# easyeda_SCH.net
KiCad netlist of a schematic drawn in EasyEDA
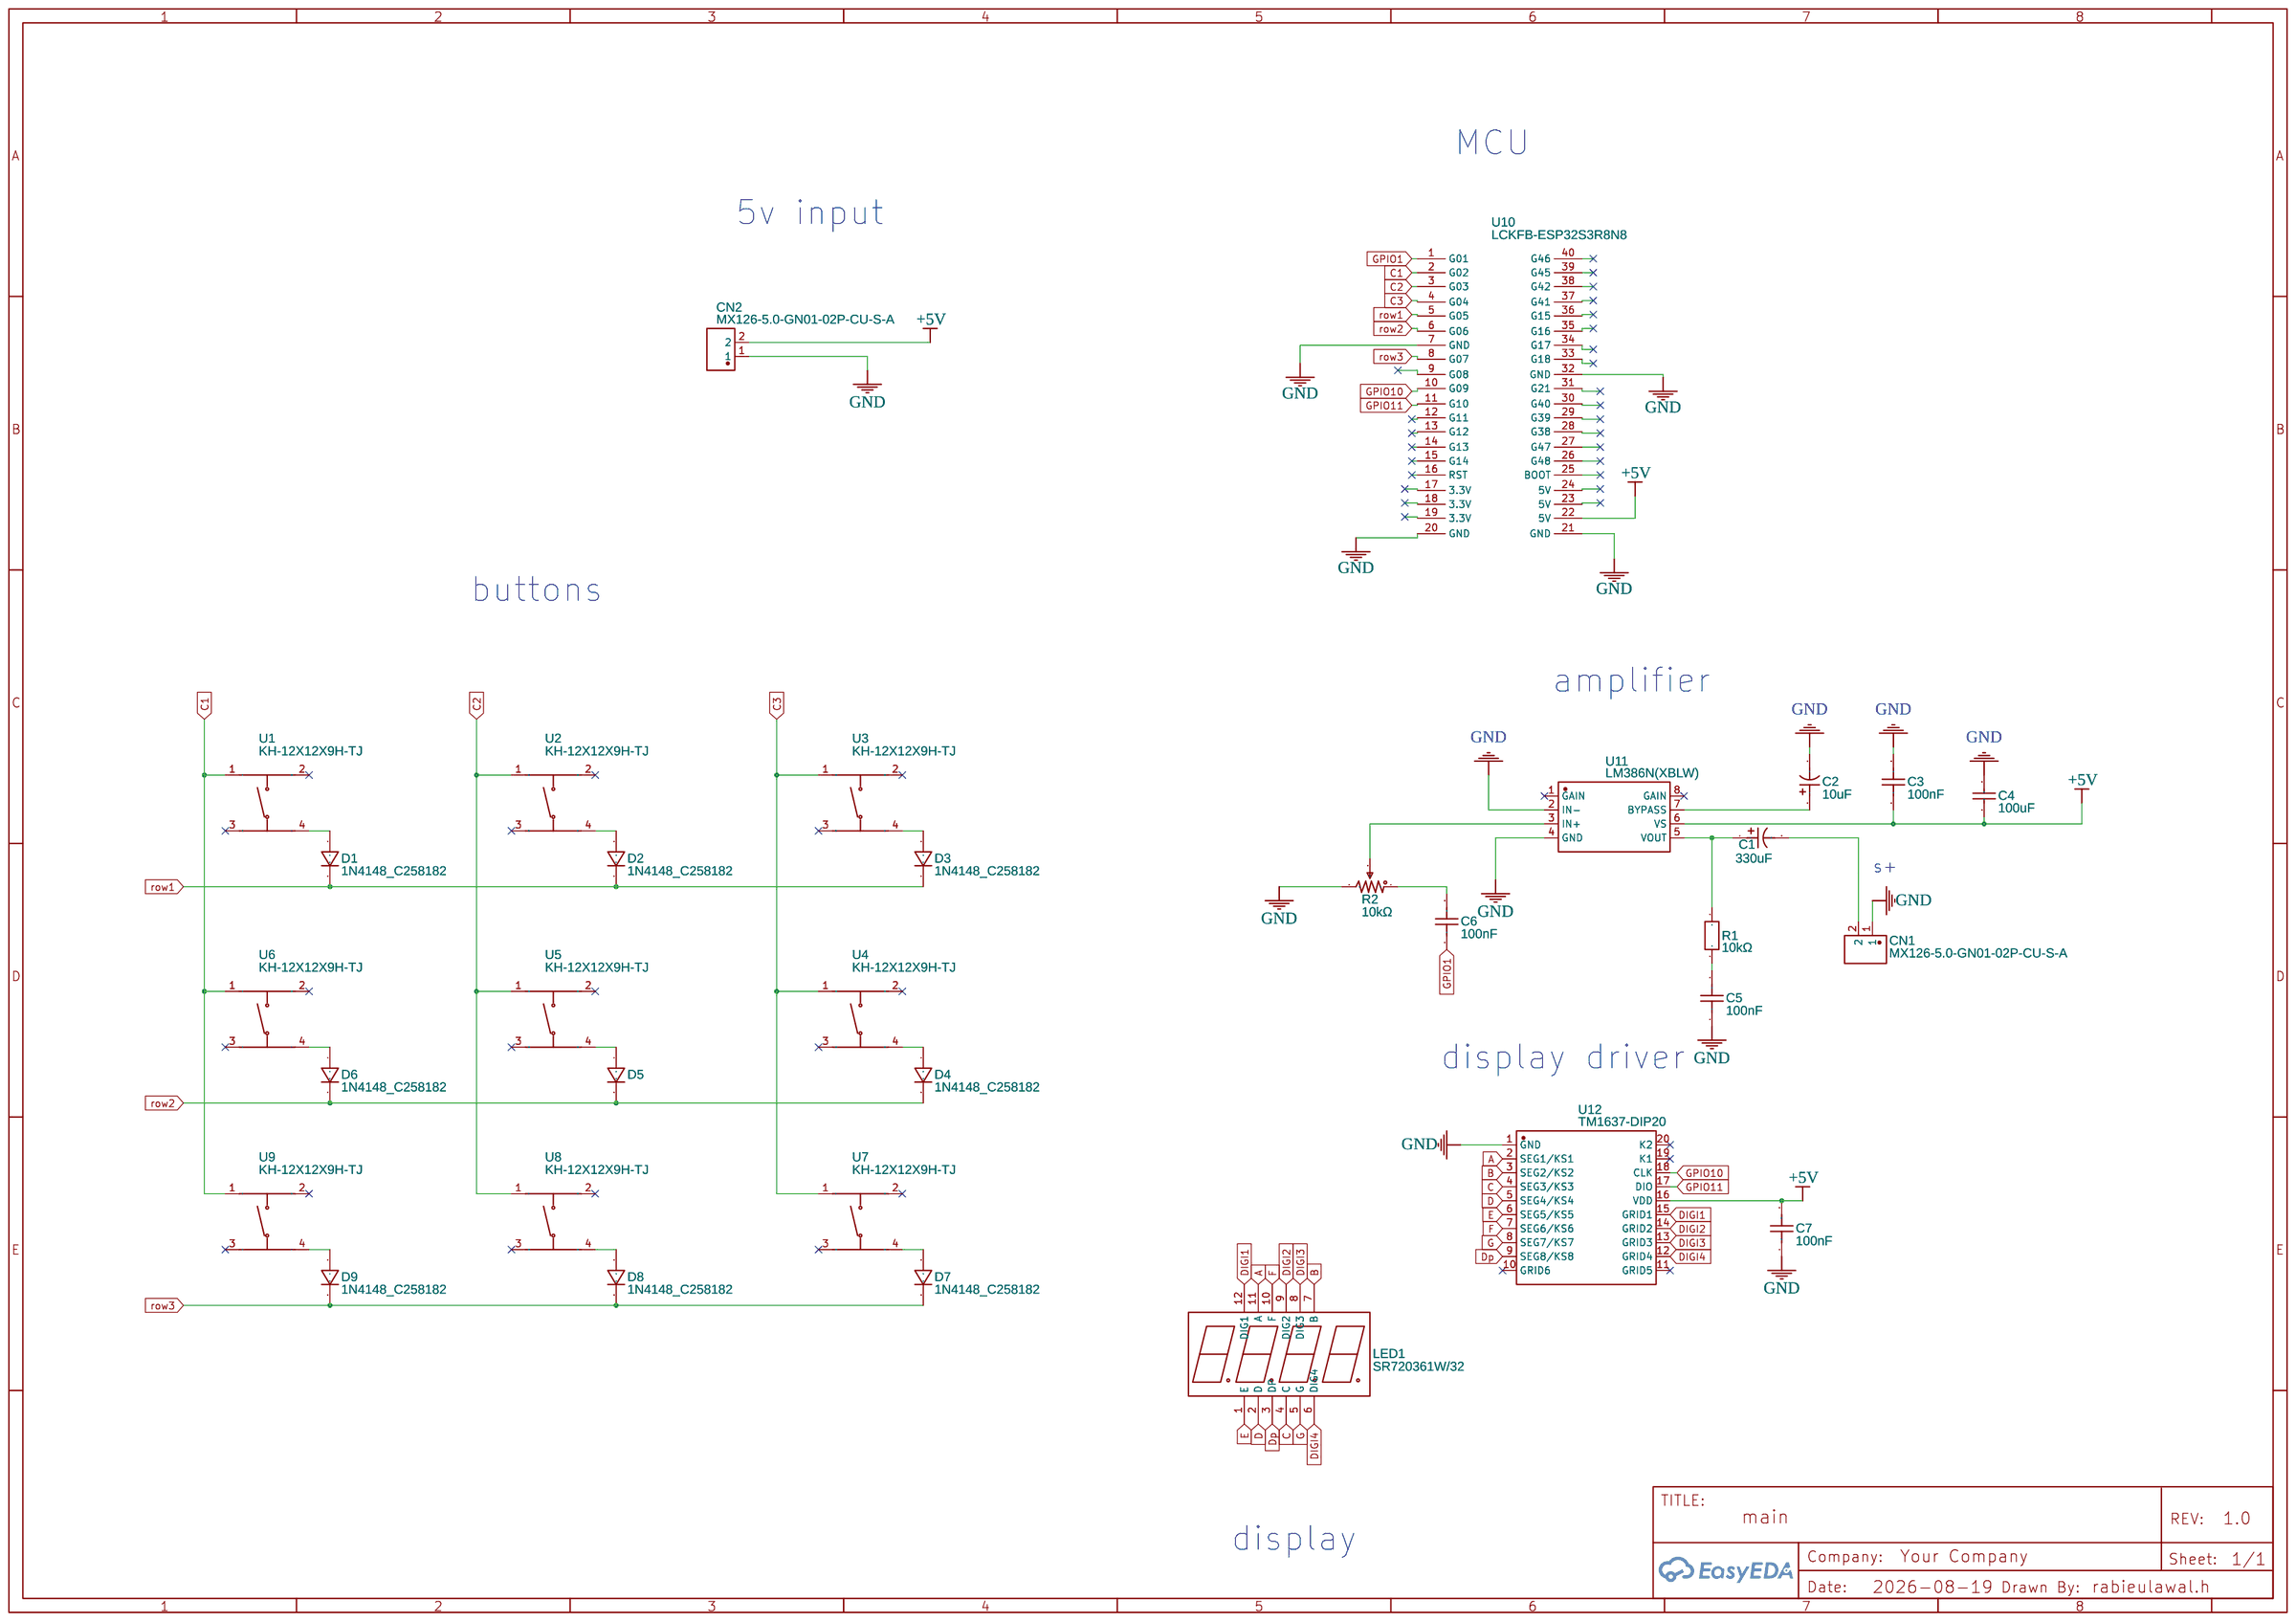
[diagram p0: schematic sheet]

(export (version "E")
  (design (tool "Eeschema 10.0.6"))
  (components
    (comp (ref "C1")
      (value "330uF")
      (fields
        (field (name "Manufacturer Part") "330uF10V6.3x11GF")
        (field (name "Manufacturer") "Econd(米朗电子)")
      )
      (libsource (lib "") (part "330UF10V6.3X11GF"))
    )
    (comp (ref "C2")
      (value "10uF")
      (fields (field (name "Manufacturer Part") "CG100ME511BP") (field (name "Manufacturer") "TWBOR(伯鸿)"))
      (libsource (lib "") (part "CG100ME511BP"))
    )
    (comp (ref "C3")
      (value "100nF")
      (fields (field (name "Manufacturer Part") "FM32X104K101EMG") (field (name "Manufacturer") "PSA(信昌电陶)"))
      (libsource (lib "") (part "FM32X104K101EMG"))
    )
    (comp (ref "C4")
      (value "100uF")
      (fields
        (field (name "Manufacturer Part") "CL32A107MQVNNNE")
        (field (name "Manufacturer") "SAMSUNG(三星)")
      )
      (libsource (lib "") (part "CL32A107MQVNNNE"))
    )
    (comp (ref "C5")
      (value "100nF")
      (fields (field (name "Manufacturer Part") "FM32X104K101EMG") (field (name "Manufacturer") "PSA(信昌电陶)"))
      (libsource (lib "") (part "FM32X104K101EMG"))
    )
    (comp (ref "C6")
      (value "100nF")
      (fields (field (name "Manufacturer Part") "FM32X104K101EMG") (field (name "Manufacturer") "PSA(信昌电陶)"))
      (libsource (lib "") (part "FM32X104K101EMG"))
    )
    (comp (ref "C7")
      (value "100nF")
      (fields (field (name "Manufacturer Part") "FM32X104K101EMG") (field (name "Manufacturer") "PSA(信昌电陶)"))
      (libsource (lib "") (part "FM32X104K101EMG"))
    )
    (comp (ref "CN1")
      (value "MX126-5.0-GN01-02P-CU-S-A")
      (fields
        (field (name "Manufacturer Part") "MX126-5.0-02P-GN01-Cu-S-A")
        (field (name "Manufacturer") "MAX(迈旭)")
      )
      (libsource (lib "") (part "MX126-5.0-GN01-02P-CU-S-A"))
    )
    (comp (ref "CN2")
      (value "MX126-5.0-GN01-02P-CU-S-A")
      (fields
        (field (name "Manufacturer Part") "MX126-5.0-02P-GN01-Cu-S-A")
        (field (name "Manufacturer") "MAX(迈旭)")
      )
      (libsource (lib "") (part "MX126-5.0-GN01-02P-CU-S-A_1"))
    )
    (comp (ref "D1")
      (value "1N4148_C258182")
      (fields (field (name "Manufacturer Part") "1N4148") (field (name "Manufacturer") "onsemi(安森美)"))
      (libsource (lib "") (part "1N4148_C258182"))
    )
    (comp (ref "D2")
      (value "1N4148_C258182")
      (fields (field (name "Manufacturer Part") "1N4148") (field (name "Manufacturer") "onsemi(安森美)"))
      (libsource (lib "") (part "1N4148_C258182"))
    )
    (comp (ref "D3")
      (value "1N4148_C258182")
      (fields (field (name "Manufacturer Part") "1N4148") (field (name "Manufacturer") "onsemi(安森美)"))
      (libsource (lib "") (part "1N4148_C258182"))
    )
    (comp (ref "D4")
      (value "1N4148_C258182")
      (fields (field (name "Manufacturer Part") "1N4148") (field (name "Manufacturer") "onsemi(安森美)"))
      (libsource (lib "") (part "1N4148_C258182"))
    )
    (comp (ref "D5")
      (value "1N4148_C258182")
      (fields (field (name "Manufacturer Part") "1N4148") (field (name "Manufacturer") "onsemi(安森美)"))
      (libsource (lib "") (part "1N4148_C258182"))
    )
    (comp (ref "D6")
      (value "1N4148_C258182")
      (fields (field (name "Manufacturer Part") "1N4148") (field (name "Manufacturer") "onsemi(安森美)"))
      (libsource (lib "") (part "1N4148_C258182"))
    )
    (comp (ref "D7")
      (value "1N4148_C258182")
      (fields (field (name "Manufacturer Part") "1N4148") (field (name "Manufacturer") "onsemi(安森美)"))
      (libsource (lib "") (part "1N4148_C258182"))
    )
    (comp (ref "D8")
      (value "1N4148_C258182")
      (fields (field (name "Manufacturer Part") "1N4148") (field (name "Manufacturer") "onsemi(安森美)"))
      (libsource (lib "") (part "1N4148_C258182"))
    )
    (comp (ref "D9")
      (value "1N4148_C258182")
      (fields (field (name "Manufacturer Part") "1N4148") (field (name "Manufacturer") "onsemi(安森美)"))
      (libsource (lib "") (part "1N4148_C258182"))
    )
    (comp (ref "LED1")
      (value "SR720361W/32")
      (fields (field (name "Manufacturer") "ARKLED(方舟)"))
      (libsource (lib "") (part "SR720361W/32"))
    )
    (comp (ref "R1")
      (value "10kΩ")
      (fields (field (name "Manufacturer Part") "CR1/8W-10K±5%-ST52") (field (name "Manufacturer") "VO(翔胜)"))
      (libsource (lib "") (part "CR1/8W-10K±5%-ST52"))
    )
    (comp (ref "R2")
      (value "10kΩ")
      (fields
        (field (name "Manufacturer Part") "RK09Y11L0001")
        (field (name "Manufacturer") "ALPSALPINE(阿尔卑斯阿尔派)")
      )
      (libsource (lib "") (part "RK09Y11L0001"))
    )
    (comp (ref "U1")
      (value "KH-12X12X9H-TJ")
      (fields (field (name "Manufacturer") "kinghelm(金航标)"))
      (libsource (lib "") (part "KH-12X12X9H-TJ"))
    )
    (comp (ref "U2")
      (value "KH-12X12X9H-TJ")
      (fields (field (name "Manufacturer") "kinghelm(金航标)"))
      (libsource (lib "") (part "KH-12X12X9H-TJ"))
    )
    (comp (ref "U3")
      (value "KH-12X12X9H-TJ")
      (fields (field (name "Manufacturer") "kinghelm(金航标)"))
      (libsource (lib "") (part "KH-12X12X9H-TJ"))
    )
    (comp (ref "U4")
      (value "KH-12X12X9H-TJ")
      (fields (field (name "Manufacturer") "kinghelm(金航标)"))
      (libsource (lib "") (part "KH-12X12X9H-TJ"))
    )
    (comp (ref "U5")
      (value "KH-12X12X9H-TJ")
      (fields (field (name "Manufacturer") "kinghelm(金航标)"))
      (libsource (lib "") (part "KH-12X12X9H-TJ"))
    )
    (comp (ref "U6")
      (value "KH-12X12X9H-TJ")
      (fields (field (name "Manufacturer") "kinghelm(金航标)"))
      (libsource (lib "") (part "KH-12X12X9H-TJ"))
    )
    (comp (ref "U7")
      (value "KH-12X12X9H-TJ")
      (fields (field (name "Manufacturer") "kinghelm(金航标)"))
      (libsource (lib "") (part "KH-12X12X9H-TJ"))
    )
    (comp (ref "U8")
      (value "KH-12X12X9H-TJ")
      (fields (field (name "Manufacturer") "kinghelm(金航标)"))
      (libsource (lib "") (part "KH-12X12X9H-TJ"))
    )
    (comp (ref "U9")
      (value "KH-12X12X9H-TJ")
      (fields (field (name "Manufacturer") "kinghelm(金航标)"))
      (libsource (lib "") (part "KH-12X12X9H-TJ"))
    )
    (comp (ref "U10")
      (value "LCKFB-ESP32S3R8N8")
      (fields (field (name "Manufacturer") "立创开发板"))
      (libsource (lib "") (part "LCKFB-ESP32S3R8N8"))
    )
    (comp (ref "U11")
      (value "LM386N(XBLW)")
      (fields (field (name "Manufacturer") "XBLW(芯伯乐)"))
      (libsource (lib "") (part "LM386N(XBLW)"))
    )
    (comp (ref "U12")
      (value "TM1637-DIP20")
      (fields (field (name "Manufacturer") "TM(天微)"))
      (libsource (lib "") (part "TM1637-DIP20"))
    )
  )
  (nets
    (net (code "1") (name "+5V") (class "Default")
      (node (ref "C3") (pin "1") (pinfunction "1_1") (pintype "unspecified"))
      (node (ref "C4") (pin "1") (pinfunction "1_1") (pintype "input"))
      (node (ref "C7") (pin "2") (pinfunction "2_2") (pintype "unspecified"))
      (node (ref "CN2") (pin "2") (pinfunction "2_2") (pintype "unspecified"))
      (node (ref "U10") (pin "22") (pinfunction "5V_22") (pintype "unspecified"))
      (node (ref "U11") (pin "6") (pinfunction "VS_6") (pintype "unspecified"))
      (node (ref "U12") (pin "16") (pinfunction "VDD_16") (pintype "unspecified"))
    )
    (net (code "2") (name "A") (class "Default")
      (node (ref "LED1") (pin "11") (pinfunction "A_11") (pintype "unspecified"))
      (node (ref "U12") (pin "2") (pinfunction "SEG1/KS1_2") (pintype "unspecified"))
    )
    (net (code "3") (name "B") (class "Default")
      (node (ref "LED1") (pin "7") (pinfunction "B_7") (pintype "unspecified"))
      (node (ref "U12") (pin "3") (pinfunction "SEG2/KS2_3") (pintype "unspecified"))
    )
    (net (code "4") (name "C") (class "Default")
      (node (ref "LED1") (pin "4") (pinfunction "C_4") (pintype "unspecified"))
      (node (ref "U12") (pin "4") (pinfunction "SEG3/KS3_4") (pintype "unspecified"))
    )
    (net (code "5") (name "C1") (class "Default")
      (node (ref "U1") (pin "1") (pinfunction "1_1") (pintype "unspecified"))
      (node (ref "U10") (pin "2") (pinfunction "G02_2") (pintype "unspecified"))
      (node (ref "U6") (pin "1") (pinfunction "1_1") (pintype "unspecified"))
      (node (ref "U9") (pin "1") (pinfunction "1_1") (pintype "unspecified"))
    )
    (net (code "6") (name "C2") (class "Default")
      (node (ref "U10") (pin "3") (pinfunction "G03_3") (pintype "unspecified"))
      (node (ref "U2") (pin "1") (pinfunction "1_1") (pintype "unspecified"))
      (node (ref "U5") (pin "1") (pinfunction "1_1") (pintype "unspecified"))
      (node (ref "U8") (pin "1") (pinfunction "1_1") (pintype "unspecified"))
    )
    (net (code "7") (name "C3") (class "Default")
      (node (ref "U10") (pin "4") (pinfunction "G04_4") (pintype "unspecified"))
      (node (ref "U3") (pin "1") (pinfunction "1_1") (pintype "unspecified"))
      (node (ref "U4") (pin "1") (pinfunction "1_1") (pintype "unspecified"))
      (node (ref "U7") (pin "1") (pinfunction "1_1") (pintype "unspecified"))
    )
    (net (code "8") (name "D") (class "Default")
      (node (ref "LED1") (pin "2") (pinfunction "D_2") (pintype "unspecified"))
      (node (ref "U12") (pin "5") (pinfunction "SEG4/KS4_5") (pintype "unspecified"))
    )
    (net (code "9") (name "DIGI1") (class "Default")
      (node (ref "LED1") (pin "12") (pinfunction "DIG1_12") (pintype "unspecified"))
      (node (ref "U12") (pin "15") (pinfunction "GRID1_15") (pintype "unspecified"))
    )
    (net (code "10") (name "DIGI2") (class "Default")
      (node (ref "LED1") (pin "9") (pinfunction "DIG2_9") (pintype "unspecified"))
      (node (ref "U12") (pin "14") (pinfunction "GRID2_14") (pintype "unspecified"))
    )
    (net (code "11") (name "DIGI3") (class "Default")
      (node (ref "LED1") (pin "8") (pinfunction "DIG3_8") (pintype "unspecified"))
      (node (ref "U12") (pin "13") (pinfunction "GRID3_13") (pintype "unspecified"))
    )
    (net (code "12") (name "DIGI4") (class "Default")
      (node (ref "LED1") (pin "6") (pinfunction "DIG4_6") (pintype "unspecified"))
      (node (ref "U12") (pin "12") (pinfunction "GRID4_12") (pintype "unspecified"))
    )
    (net (code "13") (name "Dp") (class "Default")
      (node (ref "LED1") (pin "3") (pinfunction "DP_3") (pintype "unspecified"))
      (node (ref "U12") (pin "9") (pinfunction "SEG8/KS8_9") (pintype "unspecified"))
    )
    (net (code "14") (name "E") (class "Default")
      (node (ref "LED1") (pin "1") (pinfunction "E_1") (pintype "unspecified"))
      (node (ref "U12") (pin "6") (pinfunction "SEG5/KS5_6") (pintype "unspecified"))
    )
    (net (code "15") (name "F") (class "Default")
      (node (ref "LED1") (pin "10") (pinfunction "F_10") (pintype "unspecified"))
      (node (ref "U12") (pin "7") (pinfunction "SEG6/KS6_7") (pintype "unspecified"))
    )
    (net (code "16") (name "G") (class "Default")
      (node (ref "LED1") (pin "5") (pinfunction "G_5") (pintype "unspecified"))
      (node (ref "U12") (pin "8") (pinfunction "SEG7/KS7_8") (pintype "unspecified"))
    )
    (net (code "17") (name "GND") (class "Default")
      (node (ref "C2") (pin "2") (pinfunction "2_2") (pintype "input"))
      (node (ref "C3") (pin "2") (pinfunction "2_2") (pintype "unspecified"))
      (node (ref "C4") (pin "2") (pinfunction "2_2") (pintype "input"))
      (node (ref "C5") (pin "1") (pinfunction "1_1") (pintype "unspecified"))
      (node (ref "C7") (pin "1") (pinfunction "1_1") (pintype "unspecified"))
      (node (ref "CN1") (pin "1") (pinfunction "1_1") (pintype "unspecified"))
      (node (ref "CN2") (pin "1") (pinfunction "1_1") (pintype "unspecified"))
      (node (ref "R2") (pin "3") (pinfunction "3_3") (pintype "unspecified"))
      (node (ref "U10") (pin "20") (pinfunction "GND_20") (pintype "unspecified"))
      (node (ref "U10") (pin "21") (pinfunction "GND_21") (pintype "unspecified"))
      (node (ref "U10") (pin "32") (pinfunction "GND_32") (pintype "unspecified"))
      (node (ref "U10") (pin "7") (pinfunction "GND_7") (pintype "unspecified"))
      (node (ref "U11") (pin "2") (pinfunction "IN-_2") (pintype "unspecified"))
      (node (ref "U11") (pin "4") (pinfunction "GND_4") (pintype "unspecified"))
      (node (ref "U12") (pin "1") (pinfunction "GND_1") (pintype "unspecified"))
    )
    (net (code "18") (name "GPIO1") (class "Default")
      (node (ref "C6") (pin "1") (pinfunction "1_1") (pintype "unspecified"))
      (node (ref "U10") (pin "1") (pinfunction "G01_1") (pintype "unspecified"))
    )
    (net (code "19") (name "GPIO10") (class "Default")
      (node (ref "U10") (pin "10") (pinfunction "G09_10") (pintype "unspecified"))
      (node (ref "U12") (pin "18") (pinfunction "CLK_18") (pintype "unspecified"))
    )
    (net (code "20") (name "GPIO11") (class "Default")
      (node (ref "U10") (pin "11") (pinfunction "G10_11") (pintype "unspecified"))
      (node (ref "U12") (pin "17") (pinfunction "DIO_17") (pintype "unspecified"))
    )
    (net (code "21") (name "Net-(C1-Pad2)") (class "Default")
      (node (ref "C1") (pin "2") (pinfunction "2_2") (pintype "input"))
      (node (ref "CN1") (pin "2") (pinfunction "2_2") (pintype "unspecified"))
    )
    (net (code "22") (name "Net-(C5-Pad2)") (class "Default")
      (node (ref "C5") (pin "2") (pinfunction "2_2") (pintype "unspecified"))
      (node (ref "R1") (pin "1") (pinfunction "1_1") (pintype "unspecified"))
    )
    (net (code "23") (name "Net-(C6-Pad2)") (class "Default")
      (node (ref "C6") (pin "2") (pinfunction "2_2") (pintype "unspecified"))
      (node (ref "R2") (pin "1") (pinfunction "1_1") (pintype "unspecified"))
    )
    (net (code "24") (name "Net-(D1-A)") (class "Default")
      (node (ref "D1") (pin "1") (pinfunction "A_1") (pintype "unspecified"))
      (node (ref "U1") (pin "4") (pinfunction "4_4") (pintype "unspecified"))
    )
    (net (code "25") (name "Net-(D2-A)") (class "Default")
      (node (ref "D2") (pin "1") (pinfunction "A_1") (pintype "unspecified"))
      (node (ref "U2") (pin "4") (pinfunction "4_4") (pintype "unspecified"))
    )
    (net (code "26") (name "Net-(D3-A)") (class "Default")
      (node (ref "D3") (pin "1") (pinfunction "A_1") (pintype "unspecified"))
      (node (ref "U3") (pin "4") (pinfunction "4_4") (pintype "unspecified"))
    )
    (net (code "27") (name "Net-(D4-A)") (class "Default")
      (node (ref "D4") (pin "1") (pinfunction "A_1") (pintype "unspecified"))
      (node (ref "U4") (pin "4") (pinfunction "4_4") (pintype "unspecified"))
    )
    (net (code "28") (name "Net-(D5-A)") (class "Default")
      (node (ref "D5") (pin "1") (pinfunction "A_1") (pintype "unspecified"))
      (node (ref "U5") (pin "4") (pinfunction "4_4") (pintype "unspecified"))
    )
    (net (code "29") (name "Net-(D6-A)") (class "Default")
      (node (ref "D6") (pin "1") (pinfunction "A_1") (pintype "unspecified"))
      (node (ref "U6") (pin "4") (pinfunction "4_4") (pintype "unspecified"))
    )
    (net (code "30") (name "Net-(D7-A)") (class "Default")
      (node (ref "D7") (pin "1") (pinfunction "A_1") (pintype "unspecified"))
      (node (ref "U7") (pin "4") (pinfunction "4_4") (pintype "unspecified"))
    )
    (net (code "31") (name "Net-(D8-A)") (class "Default")
      (node (ref "D8") (pin "1") (pinfunction "A_1") (pintype "unspecified"))
      (node (ref "U8") (pin "4") (pinfunction "4_4") (pintype "unspecified"))
    )
    (net (code "32") (name "Net-(D9-A)") (class "Default")
      (node (ref "D9") (pin "1") (pinfunction "A_1") (pintype "unspecified"))
      (node (ref "U9") (pin "4") (pinfunction "4_4") (pintype "unspecified"))
    )
    (net (code "33") (name "Net-(U11-BYPASS)") (class "Default")
      (node (ref "C2") (pin "1") (pinfunction "1_1") (pintype "input"))
      (node (ref "U11") (pin "7") (pinfunction "BYPASS_7") (pintype "unspecified"))
    )
    (net (code "34") (name "Net-(U11-IN+)") (class "Default")
      (node (ref "R2") (pin "2") (pinfunction "2_2") (pintype "unspecified"))
      (node (ref "U11") (pin "3") (pinfunction "IN+_3") (pintype "unspecified"))
    )
    (net (code "35") (name "Net-(U11-VOUT)") (class "Default")
      (node (ref "C1") (pin "1") (pinfunction "1_1") (pintype "input"))
      (node (ref "R1") (pin "2") (pinfunction "2_2") (pintype "unspecified"))
      (node (ref "U11") (pin "5") (pinfunction "VOUT_5") (pintype "unspecified"))
    )
    (net (code "36") (name "row1") (class "Default")
      (node (ref "D1") (pin "2") (pinfunction "K_2") (pintype "unspecified"))
      (node (ref "D2") (pin "2") (pinfunction "K_2") (pintype "unspecified"))
      (node (ref "D3") (pin "2") (pinfunction "K_2") (pintype "unspecified"))
      (node (ref "U10") (pin "5") (pinfunction "G05_5") (pintype "unspecified"))
    )
    (net (code "37") (name "row2") (class "Default")
      (node (ref "D4") (pin "2") (pinfunction "K_2") (pintype "unspecified"))
      (node (ref "D5") (pin "2") (pinfunction "K_2") (pintype "unspecified"))
      (node (ref "D6") (pin "2") (pinfunction "K_2") (pintype "unspecified"))
      (node (ref "U10") (pin "6") (pinfunction "G06_6") (pintype "unspecified"))
    )
    (net (code "38") (name "row3") (class "Default")
      (node (ref "D7") (pin "2") (pinfunction "K_2") (pintype "unspecified"))
      (node (ref "D8") (pin "2") (pinfunction "K_2") (pintype "unspecified"))
      (node (ref "D9") (pin "2") (pinfunction "K_2") (pintype "unspecified"))
      (node (ref "U10") (pin "8") (pinfunction "G07_8") (pintype "unspecified"))
    )
    (net (code "39") (name "unconnected-(U1-Pad2)") (class "Default")
      (node (ref "U1") (pin "2") (pinfunction "2_2") (pintype "unspecified+no_connect"))
    )
    (net (code "40") (name "unconnected-(U1-Pad3)") (class "Default")
      (node (ref "U1") (pin "3") (pinfunction "3_3") (pintype "unspecified+no_connect"))
    )
    (net (code "41") (name "unconnected-(U2-Pad2)") (class "Default")
      (node (ref "U2") (pin "2") (pinfunction "2_2") (pintype "unspecified+no_connect"))
    )
    (net (code "42") (name "unconnected-(U2-Pad3)") (class "Default")
      (node (ref "U2") (pin "3") (pinfunction "3_3") (pintype "unspecified+no_connect"))
    )
    (net (code "43") (name "unconnected-(U3-Pad2)") (class "Default")
      (node (ref "U3") (pin "2") (pinfunction "2_2") (pintype "unspecified+no_connect"))
    )
    (net (code "44") (name "unconnected-(U3-Pad3)") (class "Default")
      (node (ref "U3") (pin "3") (pinfunction "3_3") (pintype "unspecified+no_connect"))
    )
    (net (code "45") (name "unconnected-(U4-Pad2)") (class "Default")
      (node (ref "U4") (pin "2") (pinfunction "2_2") (pintype "unspecified+no_connect"))
    )
    (net (code "46") (name "unconnected-(U4-Pad3)") (class "Default")
      (node (ref "U4") (pin "3") (pinfunction "3_3") (pintype "unspecified+no_connect"))
    )
    (net (code "47") (name "unconnected-(U5-Pad2)") (class "Default")
      (node (ref "U5") (pin "2") (pinfunction "2_2") (pintype "unspecified+no_connect"))
    )
    (net (code "48") (name "unconnected-(U5-Pad3)") (class "Default")
      (node (ref "U5") (pin "3") (pinfunction "3_3") (pintype "unspecified+no_connect"))
    )
    (net (code "49") (name "unconnected-(U6-Pad2)") (class "Default")
      (node (ref "U6") (pin "2") (pinfunction "2_2") (pintype "unspecified+no_connect"))
    )
    (net (code "50") (name "unconnected-(U6-Pad3)") (class "Default")
      (node (ref "U6") (pin "3") (pinfunction "3_3") (pintype "unspecified+no_connect"))
    )
    (net (code "51") (name "unconnected-(U7-Pad2)") (class "Default")
      (node (ref "U7") (pin "2") (pinfunction "2_2") (pintype "unspecified+no_connect"))
    )
    (net (code "52") (name "unconnected-(U7-Pad3)") (class "Default")
      (node (ref "U7") (pin "3") (pinfunction "3_3") (pintype "unspecified+no_connect"))
    )
    (net (code "53") (name "unconnected-(U8-Pad2)") (class "Default")
      (node (ref "U8") (pin "2") (pinfunction "2_2") (pintype "unspecified+no_connect"))
    )
    (net (code "54") (name "unconnected-(U8-Pad3)") (class "Default")
      (node (ref "U8") (pin "3") (pinfunction "3_3") (pintype "unspecified+no_connect"))
    )
    (net (code "55") (name "unconnected-(U9-Pad2)") (class "Default")
      (node (ref "U9") (pin "2") (pinfunction "2_2") (pintype "unspecified+no_connect"))
    )
    (net (code "56") (name "unconnected-(U9-Pad3)") (class "Default")
      (node (ref "U9") (pin "3") (pinfunction "3_3") (pintype "unspecified+no_connect"))
    )
    (net (code "57") (name "unconnected-(U10-3.3V-Pad17)") (class "Default")
      (node (ref "U10") (pin "17") (pinfunction "3.3V_17") (pintype "unspecified+no_connect"))
    )
    (net (code "58") (name "unconnected-(U10-3.3V-Pad18)") (class "Default")
      (node (ref "U10") (pin "18") (pinfunction "3.3V_18") (pintype "unspecified+no_connect"))
    )
    (net (code "59") (name "unconnected-(U10-3.3V-Pad19)") (class "Default")
      (node (ref "U10") (pin "19") (pinfunction "3.3V_19") (pintype "unspecified+no_connect"))
    )
    (net (code "60") (name "unconnected-(U10-5V-Pad23)") (class "Default")
      (node (ref "U10") (pin "23") (pinfunction "5V_23") (pintype "unspecified+no_connect"))
    )
    (net (code "61") (name "unconnected-(U10-5V-Pad24)") (class "Default")
      (node (ref "U10") (pin "24") (pinfunction "5V_24") (pintype "unspecified+no_connect"))
    )
    (net (code "62") (name "unconnected-(U10-BOOT-Pad25)") (class "Default")
      (node (ref "U10") (pin "25") (pinfunction "BOOT_25") (pintype "unspecified+no_connect"))
    )
    (net (code "63") (name "unconnected-(U10-G08-Pad9)") (class "Default")
      (node (ref "U10") (pin "9") (pinfunction "G08_9") (pintype "unspecified+no_connect"))
    )
    (net (code "64") (name "unconnected-(U10-G11-Pad12)") (class "Default")
      (node (ref "U10") (pin "12") (pinfunction "G11_12") (pintype "unspecified+no_connect"))
    )
    (net (code "65") (name "unconnected-(U10-G12-Pad13)") (class "Default")
      (node (ref "U10") (pin "13") (pinfunction "G12_13") (pintype "unspecified+no_connect"))
    )
    (net (code "66") (name "unconnected-(U10-G13-Pad14)") (class "Default")
      (node (ref "U10") (pin "14") (pinfunction "G13_14") (pintype "unspecified+no_connect"))
    )
    (net (code "67") (name "unconnected-(U10-G14-Pad15)") (class "Default")
      (node (ref "U10") (pin "15") (pinfunction "G14_15") (pintype "unspecified+no_connect"))
    )
    (net (code "68") (name "unconnected-(U10-G15-Pad36)") (class "Default")
      (node (ref "U10") (pin "36") (pinfunction "G15_36") (pintype "unspecified+no_connect"))
    )
    (net (code "69") (name "unconnected-(U10-G16-Pad35)") (class "Default")
      (node (ref "U10") (pin "35") (pinfunction "G16_35") (pintype "unspecified+no_connect"))
    )
    (net (code "70") (name "unconnected-(U10-G17-Pad34)") (class "Default")
      (node (ref "U10") (pin "34") (pinfunction "G17_34") (pintype "unspecified+no_connect"))
    )
    (net (code "71") (name "unconnected-(U10-G18-Pad33)") (class "Default")
      (node (ref "U10") (pin "33") (pinfunction "G18_33") (pintype "unspecified+no_connect"))
    )
    (net (code "72") (name "unconnected-(U10-G21-Pad31)") (class "Default")
      (node (ref "U10") (pin "31") (pinfunction "G21_31") (pintype "unspecified+no_connect"))
    )
    (net (code "73") (name "unconnected-(U10-G38-Pad28)") (class "Default")
      (node (ref "U10") (pin "28") (pinfunction "G38_28") (pintype "unspecified+no_connect"))
    )
    (net (code "74") (name "unconnected-(U10-G39-Pad29)") (class "Default")
      (node (ref "U10") (pin "29") (pinfunction "G39_29") (pintype "unspecified+no_connect"))
    )
    (net (code "75") (name "unconnected-(U10-G40-Pad30)") (class "Default")
      (node (ref "U10") (pin "30") (pinfunction "G40_30") (pintype "unspecified+no_connect"))
    )
    (net (code "76") (name "unconnected-(U10-G41-Pad37)") (class "Default")
      (node (ref "U10") (pin "37") (pinfunction "G41_37") (pintype "unspecified+no_connect"))
    )
    (net (code "77") (name "unconnected-(U10-G42-Pad38)") (class "Default")
      (node (ref "U10") (pin "38") (pinfunction "G42_38") (pintype "unspecified+no_connect"))
    )
    (net (code "78") (name "unconnected-(U10-G45-Pad39)") (class "Default")
      (node (ref "U10") (pin "39") (pinfunction "G45_39") (pintype "unspecified+no_connect"))
    )
    (net (code "79") (name "unconnected-(U10-G46-Pad40)") (class "Default")
      (node (ref "U10") (pin "40") (pinfunction "G46_40") (pintype "unspecified+no_connect"))
    )
    (net (code "80") (name "unconnected-(U10-G47-Pad27)") (class "Default")
      (node (ref "U10") (pin "27") (pinfunction "G47_27") (pintype "unspecified+no_connect"))
    )
    (net (code "81") (name "unconnected-(U10-G48-Pad26)") (class "Default")
      (node (ref "U10") (pin "26") (pinfunction "G48_26") (pintype "unspecified+no_connect"))
    )
    (net (code "82") (name "unconnected-(U10-RST-Pad16)") (class "Default")
      (node (ref "U10") (pin "16") (pinfunction "RST_16") (pintype "unspecified+no_connect"))
    )
    (net (code "83") (name "unconnected-(U11-GAIN-Pad1)") (class "Default")
      (node (ref "U11") (pin "1") (pinfunction "GAIN_1") (pintype "unspecified+no_connect"))
    )
    (net (code "84") (name "unconnected-(U11-GAIN-Pad8)") (class "Default")
      (node (ref "U11") (pin "8") (pinfunction "GAIN_8") (pintype "unspecified+no_connect"))
    )
    (net (code "85") (name "unconnected-(U12-GRID5-Pad11)") (class "Default")
      (node (ref "U12") (pin "11") (pinfunction "GRID5_11") (pintype "unspecified+no_connect"))
    )
    (net (code "86") (name "unconnected-(U12-GRID6-Pad10)") (class "Default")
      (node (ref "U12") (pin "10") (pinfunction "GRID6_10") (pintype "unspecified+no_connect"))
    )
    (net (code "87") (name "unconnected-(U12-K1-Pad19)") (class "Default")
      (node (ref "U12") (pin "19") (pinfunction "K1_19") (pintype "unspecified+no_connect"))
    )
    (net (code "88") (name "unconnected-(U12-K2-Pad20)") (class "Default")
      (node (ref "U12") (pin "20") (pinfunction "K2_20") (pintype "unspecified+no_connect"))
    )
  )
)
